# Ocreeb_MK_2__dials_half__schematic.net
KiCad netlist of a schematic drawn in EAGLE
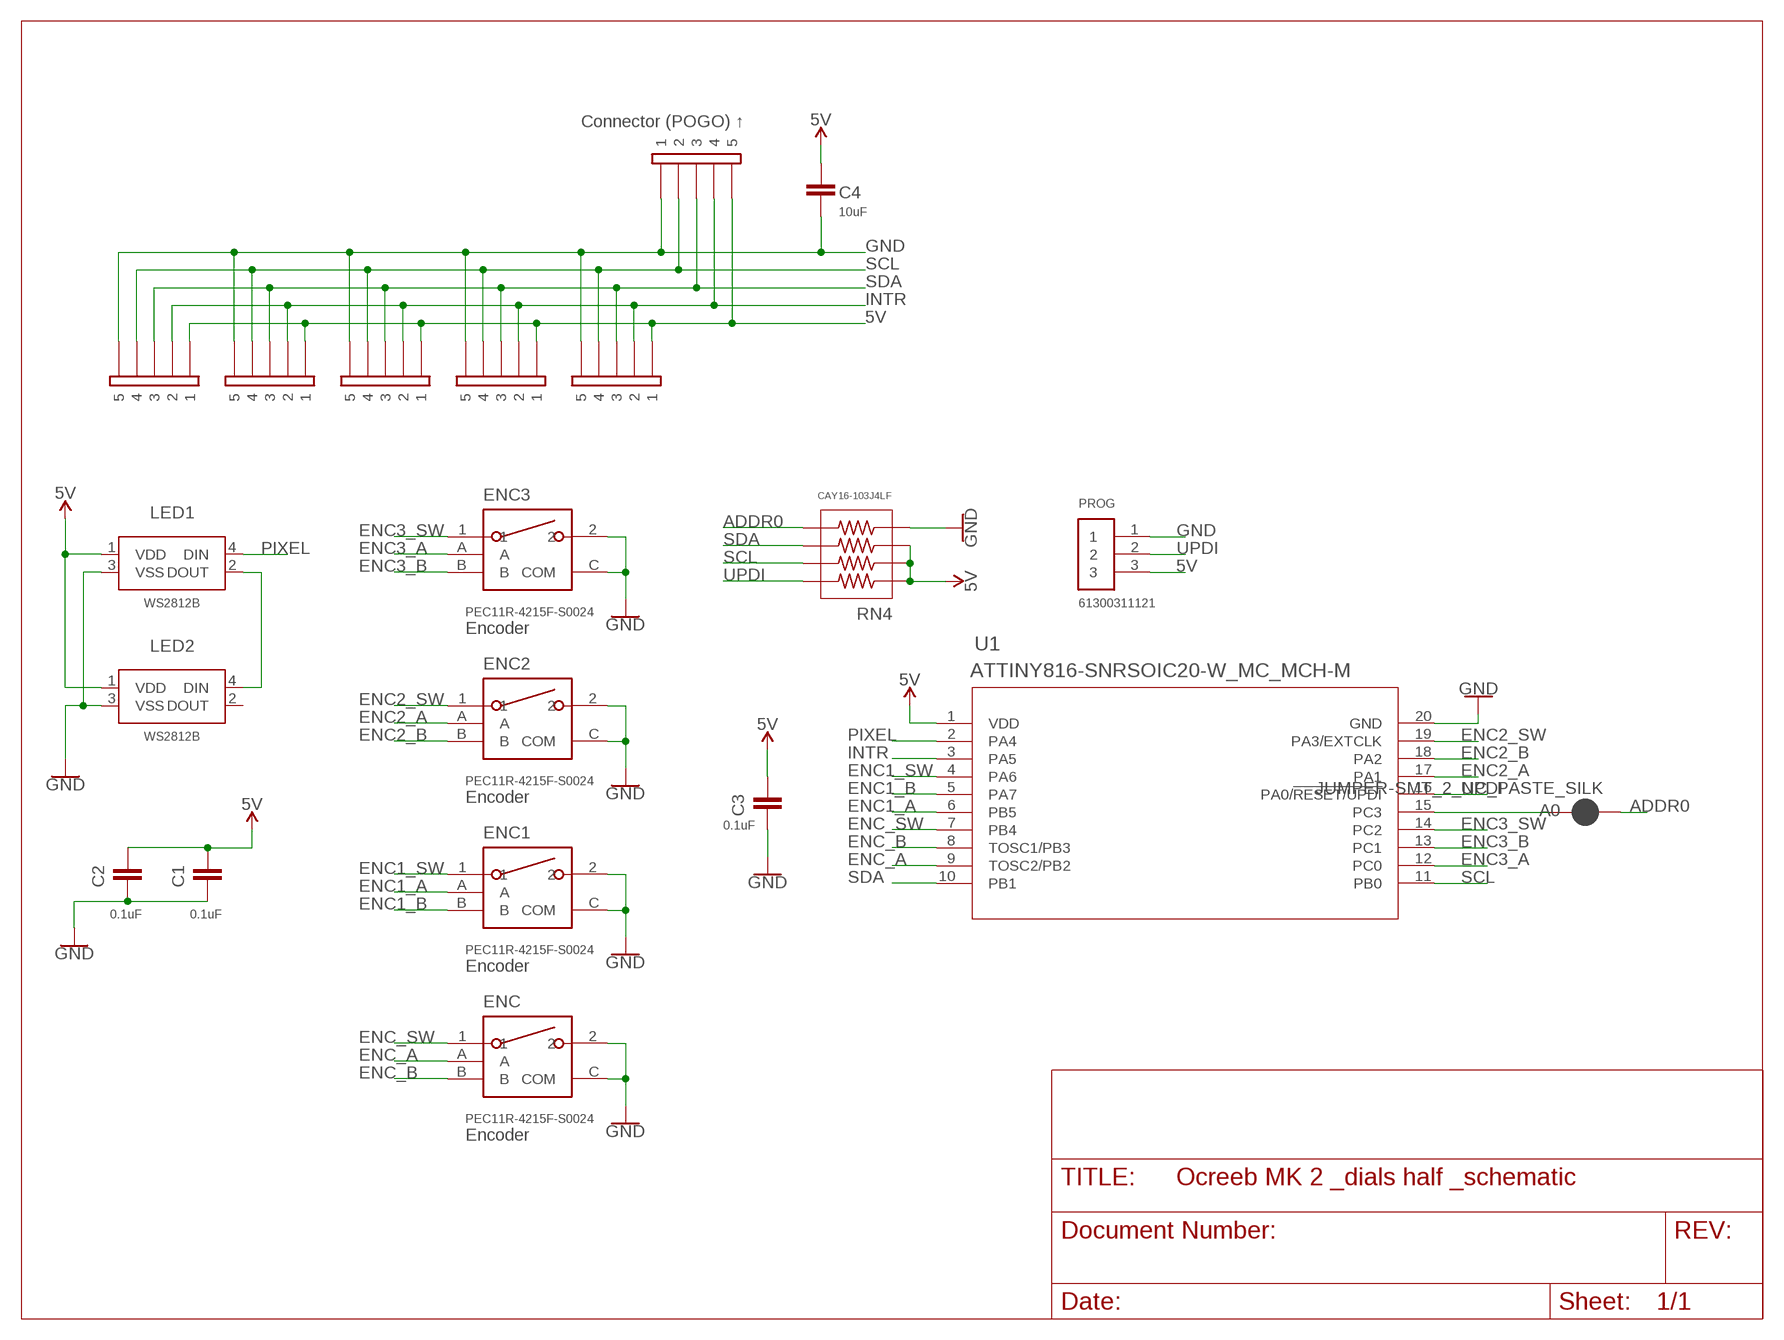
[diagram p0: schematic, sheet 1]

(export (version "E")
  (design (tool "Eeschema 10.0.6"))
  (components
    (comp (ref "A0")
      (value "JUMPER-SMT_2_NC_PASTE_SILK")
      (footprint "eagle-import:SMT-JUMPER_2_NC_PASTE_SILK")
      (libsource (lib "eagle-import") (part "JUMPER-SMT_2_NC_PASTE_SILK"))
    )
    (comp (ref "C1")
      (value "0.1uF")
      (footprint "eagle-import:CAPC1608X85")
      (libsource (lib "eagle-import") (part "CCHIP-0603(1608-METRIC)_"))
    )
    (comp (ref "C2")
      (value "0.1uF")
      (footprint "eagle-import:CAPC1608X85")
      (libsource (lib "eagle-import") (part "CCHIP-0603(1608-METRIC)_"))
    )
    (comp (ref "C3")
      (value "0.1uF")
      (footprint "eagle-import:CAPC1608X85")
      (libsource (lib "eagle-import") (part "CCHIP-0603(1608-METRIC)_"))
    )
    (comp (ref "C4")
      (value "10uF")
      (footprint "eagle-import:CAPC2012X110")
      (libsource (lib "eagle-import") (part "CCHIP-0805(2012-METRIC)_"))
    )
    (comp (ref "ENC")
      (value "PEC11R-4215F-S0024")
      (footprint "eagle-import:PEC11R-4215F-S0024")
      (fields
        (field (name "DIGIKEY_PART_NUMBER") "PEC11R-4215F-S0024-ND")
        (field (name "MANUFACTURER") "Bourns Inc.")
        (field (name "CREATED_BY") "PCBLayout.com")
      )
      (libsource (lib "eagle-import") (part "PEC11R-4215F-S0024"))
    )
    (comp (ref "ENC1")
      (value "PEC11R-4215F-S0024")
      (footprint "eagle-import:PEC11R-4215F-S0024")
      (fields
        (field (name "DIGIKEY_PART_NUMBER") "PEC11R-4215F-S0024-ND")
        (field (name "MANUFACTURER") "Bourns Inc.")
        (field (name "CREATED_BY") "PCBLayout.com")
      )
      (libsource (lib "eagle-import") (part "PEC11R-4215F-S0024"))
    )
    (comp (ref "ENC2")
      (value "PEC11R-4215F-S0024")
      (footprint "eagle-import:PEC11R-4215F-S0024")
      (fields
        (field (name "DIGIKEY_PART_NUMBER") "PEC11R-4215F-S0024-ND")
        (field (name "MANUFACTURER") "Bourns Inc.")
        (field (name "CREATED_BY") "PCBLayout.com")
      )
      (libsource (lib "eagle-import") (part "PEC11R-4215F-S0024"))
    )
    (comp (ref "ENC3")
      (value "PEC11R-4215F-S0024")
      (footprint "eagle-import:PEC11R-4215F-S0024")
      (fields
        (field (name "DIGIKEY_PART_NUMBER") "PEC11R-4215F-S0024-ND")
        (field (name "MANUFACTURER") "Bourns Inc.")
        (field (name "CREATED_BY") "PCBLayout.com")
      )
      (libsource (lib "eagle-import") (part "PEC11R-4215F-S0024"))
    )
    (comp (ref "LED1")
      (value "WS2812B")
      (footprint "eagle-import:WS2812B")
      (fields (field (name "MANUFACTURER") "Worldsemi"))
      (libsource (lib "eagle-import") (part "WS2812B"))
    )
    (comp (ref "LED2")
      (value "WS2812B")
      (footprint "eagle-import:WS2812B")
      (fields (field (name "MANUFACTURER") "Worldsemi"))
      (libsource (lib "eagle-import") (part "WS2812B"))
    )
    (comp (ref "PROG")
      (value "61300311121")
      (footprint "eagle-import:61300311121")
      (fields
        (field (name "DIGI_KEY_PART_NUMBER") "732-5316-ND")
        (field (name "MANUFACTURER") "Wurth Electronics Inc.")
        (field (name "CREATED_BY") "PCBLayout.com")
      )
      (libsource (lib "eagle-import") (part "61300311121"))
    )
    (comp (ref "RN4")
      (value "CAY16-103J4LF")
      (footprint "eagle-import:RESCAF80P320X160X60-8N")
      (fields (field (name "DIGIKEY_PART_NUMBER") "CAY16-103J4LFTR-ND") (field (name "MF") "Bourns"))
      (libsource (lib "eagle-import") (part "CAY16-103J4LF"))
    )
    (comp (ref "U$1")
      (value "5PIN_EDGE5_POGO_EDGE_OUT_")
      (footprint "eagle-import:5_POGO_EDGE")
      (libsource (lib "eagle-import") (part "5PIN_EDGE5_POGO_EDGE_OUT_"))
    )
    (comp (ref "U$2")
      (value "5PIN_EDGE")
      (footprint "eagle-import:5_POGO_EDGE")
      (libsource (lib "eagle-import") (part "5PIN_EDGE"))
    )
    (comp (ref "U$3")
      (value "5PIN_EDGE")
      (footprint "eagle-import:5_POGO_EDGE")
      (libsource (lib "eagle-import") (part "5PIN_EDGE"))
    )
    (comp (ref "U$4")
      (value "5PIN_EDGE")
      (footprint "eagle-import:5_POGO_EDGE")
      (libsource (lib "eagle-import") (part "5PIN_EDGE"))
    )
    (comp (ref "U$5")
      (value "5PIN_EDGE")
      (footprint "eagle-import:5_POGO_EDGE")
      (libsource (lib "eagle-import") (part "5PIN_EDGE"))
    )
    (comp (ref "U$6")
      (value "5PIN_EDGE")
      (footprint "eagle-import:5_POGO_EDGE")
      (libsource (lib "eagle-import") (part "5PIN_EDGE"))
    )
    (comp (ref "U1")
      (value "ATTINY816-SNRSOIC20-W_MC_MCH-M")
      (footprint "eagle-import:SOIC20-W_MC_MCH-M")
      (fields
        (field (name "MANUFACTURER_PART_NUMBER") "ATTINY816-SNR")
        (field (name "COPYRIGHT") "Copyright (C) 2023 Ultra Librarian. All rights reserved.")
      )
      (libsource (lib "eagle-import") (part "ATTINY816-SNRSOIC20-W_MC_MCH-M"))
    )
  )
  (nets
    (net (code "1") (name "/ADDR0") (class "Default")
      (node (ref "A0") (pin "1") (pinfunction "1_1") (pintype "passive"))
      (node (ref "RN4") (pin "5") (pinfunction "5_5") (pintype "passive"))
    )
    (net (code "2") (name "/ENC1_A") (class "Default")
      (node (ref "ENC1") (pin "A") (pinfunction "A_A") (pintype "passive"))
      (node (ref "U1") (pin "6") (pinfunction "PB5_6") (pintype "bidirectional"))
    )
    (net (code "3") (name "/ENC1_B") (class "Default")
      (node (ref "ENC1") (pin "B") (pinfunction "B_B") (pintype "passive"))
      (node (ref "U1") (pin "5") (pinfunction "PA7_5") (pintype "bidirectional"))
    )
    (net (code "4") (name "/ENC1_SW") (class "Default")
      (node (ref "ENC1") (pin "1") (pinfunction "1_1") (pintype "passive"))
      (node (ref "U1") (pin "4") (pinfunction "PA6_4") (pintype "bidirectional"))
    )
    (net (code "5") (name "/ENC2_A") (class "Default")
      (node (ref "ENC2") (pin "A") (pinfunction "A_A") (pintype "passive"))
      (node (ref "U1") (pin "17") (pinfunction "PA1_17") (pintype "bidirectional"))
    )
    (net (code "6") (name "/ENC2_B") (class "Default")
      (node (ref "ENC2") (pin "B") (pinfunction "B_B") (pintype "passive"))
      (node (ref "U1") (pin "18") (pinfunction "PA2_18") (pintype "bidirectional"))
    )
    (net (code "7") (name "/ENC2_SW") (class "Default")
      (node (ref "ENC2") (pin "1") (pinfunction "1_1") (pintype "passive"))
      (node (ref "U1") (pin "19") (pinfunction "PA3/EXTCLK_19") (pintype "bidirectional"))
    )
    (net (code "8") (name "/ENC3_A") (class "Default")
      (node (ref "ENC3") (pin "A") (pinfunction "A_A") (pintype "passive"))
      (node (ref "U1") (pin "12") (pinfunction "PC0_12") (pintype "bidirectional"))
    )
    (net (code "9") (name "/ENC3_B") (class "Default")
      (node (ref "ENC3") (pin "B") (pinfunction "B_B") (pintype "passive"))
      (node (ref "U1") (pin "13") (pinfunction "PC1_13") (pintype "bidirectional"))
    )
    (net (code "10") (name "/ENC3_SW") (class "Default")
      (node (ref "ENC3") (pin "1") (pinfunction "1_1") (pintype "passive"))
      (node (ref "U1") (pin "14") (pinfunction "PC2_14") (pintype "bidirectional"))
    )
    (net (code "11") (name "/ENC_A") (class "Default")
      (node (ref "ENC") (pin "A") (pinfunction "A_A") (pintype "passive"))
      (node (ref "U1") (pin "9") (pinfunction "TOSC2/PB2_9") (pintype "bidirectional"))
    )
    (net (code "12") (name "/ENC_B") (class "Default")
      (node (ref "ENC") (pin "B") (pinfunction "B_B") (pintype "passive"))
      (node (ref "U1") (pin "8") (pinfunction "TOSC1/PB3_8") (pintype "bidirectional"))
    )
    (net (code "13") (name "/ENC_SW") (class "Default")
      (node (ref "ENC") (pin "1") (pinfunction "1_1") (pintype "passive"))
      (node (ref "U1") (pin "7") (pinfunction "PB4_7") (pintype "bidirectional"))
    )
    (net (code "14") (name "/INTR") (class "Default")
      (node (ref "U$1") (pin "4") (pinfunction "4_4") (pintype "bidirectional"))
      (node (ref "U$2") (pin "2") (pinfunction "2_2") (pintype "bidirectional"))
      (node (ref "U$3") (pin "2") (pinfunction "2_2") (pintype "bidirectional"))
      (node (ref "U$4") (pin "2") (pinfunction "2_2") (pintype "bidirectional"))
      (node (ref "U$5") (pin "2") (pinfunction "2_2") (pintype "bidirectional"))
      (node (ref "U$6") (pin "2") (pinfunction "2_2") (pintype "bidirectional"))
      (node (ref "U1") (pin "3") (pinfunction "PA5_3") (pintype "bidirectional"))
    )
    (net (code "15") (name "/PIXEL") (class "Default")
      (node (ref "LED1") (pin "4") (pinfunction "DIN_4") (pintype "input"))
      (node (ref "U1") (pin "2") (pinfunction "PA4_2") (pintype "bidirectional"))
    )
    (net (code "16") (name "/SCL") (class "Default")
      (node (ref "RN4") (pin "7") (pinfunction "7_7") (pintype "passive"))
      (node (ref "U$1") (pin "2") (pinfunction "2_2") (pintype "bidirectional"))
      (node (ref "U$2") (pin "4") (pinfunction "4_4") (pintype "bidirectional"))
      (node (ref "U$3") (pin "4") (pinfunction "4_4") (pintype "bidirectional"))
      (node (ref "U$4") (pin "4") (pinfunction "4_4") (pintype "bidirectional"))
      (node (ref "U$5") (pin "4") (pinfunction "4_4") (pintype "bidirectional"))
      (node (ref "U$6") (pin "4") (pinfunction "4_4") (pintype "bidirectional"))
      (node (ref "U1") (pin "11") (pinfunction "PB0_11") (pintype "bidirectional"))
    )
    (net (code "17") (name "/SDA") (class "Default")
      (node (ref "RN4") (pin "6") (pinfunction "6_6") (pintype "passive"))
      (node (ref "U$1") (pin "3") (pinfunction "3_3") (pintype "bidirectional"))
      (node (ref "U$2") (pin "3") (pinfunction "3_3") (pintype "bidirectional"))
      (node (ref "U$3") (pin "3") (pinfunction "3_3") (pintype "bidirectional"))
      (node (ref "U$4") (pin "3") (pinfunction "3_3") (pintype "bidirectional"))
      (node (ref "U$5") (pin "3") (pinfunction "3_3") (pintype "bidirectional"))
      (node (ref "U$6") (pin "3") (pinfunction "3_3") (pintype "bidirectional"))
      (node (ref "U1") (pin "10") (pinfunction "PB1_10") (pintype "bidirectional"))
    )
    (net (code "18") (name "/UPDI") (class "Default")
      (node (ref "PROG") (pin "2") (pinfunction "2_2") (pintype "passive"))
      (node (ref "RN4") (pin "8") (pinfunction "8_8") (pintype "passive"))
      (node (ref "U1") (pin "16") (pinfunction "PA0/~{RESET/UPDI}_16") (pintype "bidirectional"))
    )
    (net (code "19") (name "5V") (class "Default")
      (node (ref "C1") (pin "2") (pinfunction "2_2") (pintype "passive"))
      (node (ref "C2") (pin "2") (pinfunction "2_2") (pintype "passive"))
      (node (ref "C3") (pin "2") (pinfunction "2_2") (pintype "passive"))
      (node (ref "C4") (pin "2") (pinfunction "2_2") (pintype "passive"))
      (node (ref "LED1") (pin "1") (pinfunction "VDD_1") (pintype "power_in"))
      (node (ref "LED2") (pin "1") (pinfunction "VDD_1") (pintype "power_in"))
      (node (ref "PROG") (pin "3") (pinfunction "3_3") (pintype "passive"))
      (node (ref "RN4") (pin "1") (pinfunction "1_1") (pintype "passive"))
      (node (ref "RN4") (pin "2") (pinfunction "2_2") (pintype "passive"))
      (node (ref "RN4") (pin "3") (pinfunction "3_3") (pintype "passive"))
      (node (ref "U$1") (pin "5") (pinfunction "5_5") (pintype "bidirectional"))
      (node (ref "U$2") (pin "1") (pinfunction "1_1") (pintype "bidirectional"))
      (node (ref "U$3") (pin "1") (pinfunction "1_1") (pintype "bidirectional"))
      (node (ref "U$4") (pin "1") (pinfunction "1_1") (pintype "bidirectional"))
      (node (ref "U$5") (pin "1") (pinfunction "1_1") (pintype "bidirectional"))
      (node (ref "U$6") (pin "1") (pinfunction "1_1") (pintype "bidirectional"))
      (node (ref "U1") (pin "1") (pinfunction "VDD_1") (pintype "power_in"))
    )
    (net (code "20") (name "GND") (class "Default")
      (node (ref "C1") (pin "1") (pinfunction "1_1") (pintype "passive"))
      (node (ref "C2") (pin "1") (pinfunction "1_1") (pintype "passive"))
      (node (ref "C3") (pin "1") (pinfunction "1_1") (pintype "passive"))
      (node (ref "C4") (pin "1") (pinfunction "1_1") (pintype "passive"))
      (node (ref "ENC") (pin "2") (pinfunction "2_2") (pintype "passive"))
      (node (ref "ENC") (pin "C") (pinfunction "COM_C") (pintype "passive"))
      (node (ref "ENC1") (pin "2") (pinfunction "2_2") (pintype "passive"))
      (node (ref "ENC1") (pin "C") (pinfunction "COM_C") (pintype "passive"))
      (node (ref "ENC2") (pin "2") (pinfunction "2_2") (pintype "passive"))
      (node (ref "ENC2") (pin "C") (pinfunction "COM_C") (pintype "passive"))
      (node (ref "ENC3") (pin "2") (pinfunction "2_2") (pintype "passive"))
      (node (ref "ENC3") (pin "C") (pinfunction "COM_C") (pintype "passive"))
      (node (ref "LED1") (pin "3") (pinfunction "VSS_3") (pintype "power_in"))
      (node (ref "LED2") (pin "3") (pinfunction "VSS_3") (pintype "power_in"))
      (node (ref "PROG") (pin "1") (pinfunction "1_1") (pintype "passive"))
      (node (ref "RN4") (pin "4") (pinfunction "4_4") (pintype "passive"))
      (node (ref "U$1") (pin "1") (pinfunction "1_1") (pintype "bidirectional"))
      (node (ref "U$2") (pin "5") (pinfunction "5_5") (pintype "bidirectional"))
      (node (ref "U$3") (pin "5") (pinfunction "5_5") (pintype "bidirectional"))
      (node (ref "U$4") (pin "5") (pinfunction "5_5") (pintype "bidirectional"))
      (node (ref "U$5") (pin "5") (pinfunction "5_5") (pintype "bidirectional"))
      (node (ref "U$6") (pin "5") (pinfunction "5_5") (pintype "bidirectional"))
      (node (ref "U1") (pin "20") (pinfunction "GND_20") (pintype "passive"))
    )
    (net (code "21") (name "Net-(LED1-DOUT)") (class "Default")
      (node (ref "LED1") (pin "2") (pinfunction "DOUT_2") (pintype "output"))
      (node (ref "LED2") (pin "4") (pinfunction "DIN_4") (pintype "input"))
    )
    (net (code "22") (name "Net-(U1-PC3)") (class "Default")
      (node (ref "A0") (pin "2") (pinfunction "2_2") (pintype "passive"))
      (node (ref "U1") (pin "15") (pinfunction "PC3_15") (pintype "bidirectional"))
    )
    (net (code "23") (name "unconnected-(LED2-DOUT-Pad2)") (class "Default")
      (node (ref "LED2") (pin "2") (pinfunction "DOUT_2") (pintype "output"))
    )
  )
)
